# Sheet-QBOOST-v0_2.net
KiCad netlist of a schematic drawn in Altium Designer
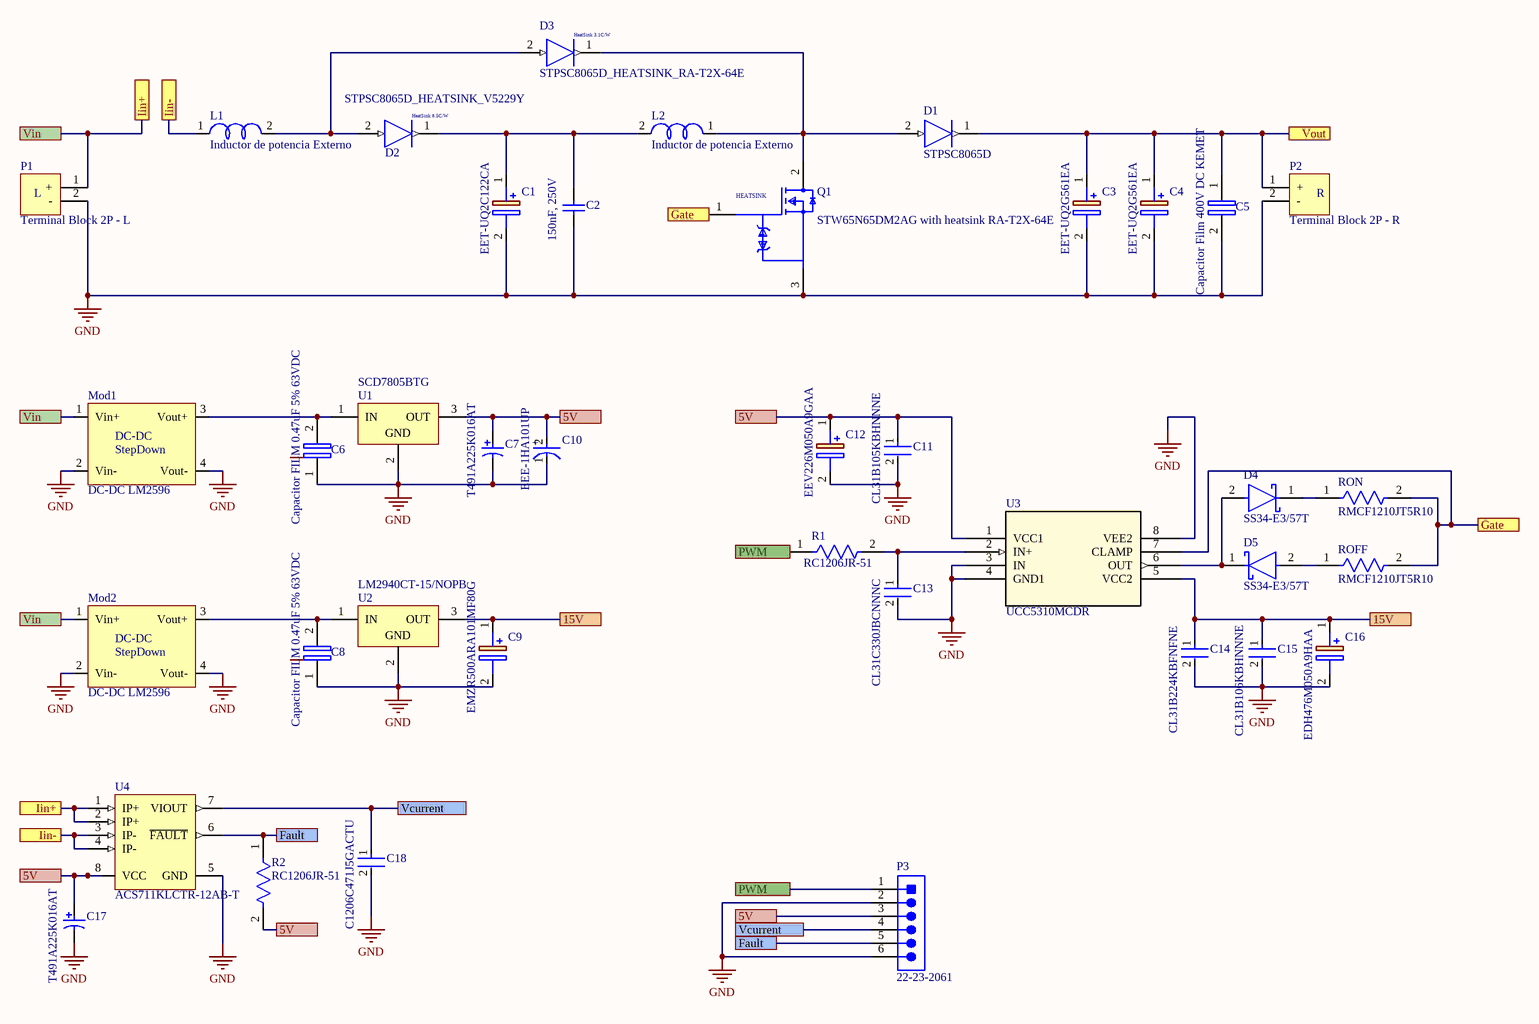
[diagram p0: Sheet-QBOOST-v0.2.SchDoc]

(export (version "E")
  (design (tool "Eeschema 10.0.6"))
  (components
    (comp (ref "C1")
      (value "EET-UQ2C122CA")
      (footprint "SamacSys:CAPPRD1000W200D2550H3700")
      (description "Capacitor Polarised")
      (libsource (lib "SamacSys") (part "EET-UQ2C122CA"))
    )
    (comp (ref "C2")
      (value "150nF, 250V")
      (footprint "WCAP-FTBP_L10.5W5H11")
      (description "WCAP-FTBP Film Capacitor, THT, L10.5W5H11, 150nF, 250V")
      (fields
        (field (name "MANUFACTURER") "Wurth Elektronik")
        (field (name "MANUFACTURER PART NUMBER") "890273322005CS")
      )
      (libsource (lib "890273322005CS_Alitum_WCAP-FTBP_rev20a") (part "890273322005CS"))
    )
    (comp (ref "C3")
      (value "EET-UQ2G561EA")
      (footprint "SamacSys:CAPPRD1000W200D3550H3700")
      (description "Capacitor Polarised")
      (libsource (lib "SamacSys") (part "EET-UQ2G561EA"))
    )
    (comp (ref "C4")
      (value "EET-UQ2G561EA")
      (footprint "SamacSys:CAPPRD1000W200D3550H3700")
      (description "Capacitor Polarised")
      (libsource (lib "SamacSys") (part "EET-UQ2G561EA"))
    )
    (comp (ref "C5")
      (value "Capacitor Film 400V DC KEMET")
      (footprint "Cap Film 18x5")
      (libsource (lib "CapFilm") (part "Cap film 400V DC 0.1uF"))
    )
    (comp (ref "C6")
      (value "Capacitor FILM 0.47uF 5% 63VDC")
      (footprint "Capacitor 5mm Radial")
      (libsource (lib "CAP FILM 0.47UF 5% 63VDC") (part "Capacitor FILM 0.47uF 5% 63VDC"))
    )
    (comp (ref "C7")
      (value "T491A225K016AT")
      (footprint "KEMT-T491-A_N")
      (description "Tantalum Capacitor, 2.2 uF, +/- 10%, 16 V, -55 to 125 degC, 2-Pin SMD, RoHS, Tape and Reel")
      (fields (field (name "VOLTAGE") "16VDC") (field (name "MANUFACTURER") "Kemet"))
      (libsource (lib "Altium Content Vault") (part "CAP-P-2"))
    )
    (comp (ref "C8")
      (value "Capacitor FILM 0.47uF 5% 63VDC")
      (footprint "Capacitor 5mm Radial")
      (libsource (lib "CAP FILM 0.47UF 5% 63VDC") (part "Capacitor FILM 0.47uF 5% 63VDC"))
    )
    (comp (ref "C9")
      (value "EMZR500ARA101MF80G")
      (footprint "CAP6.3X8")
      (description "CAP ALUM 100UF 20% 50V SMD")
      (libsource (lib "SamacSys") (part "EMZR500ARA101MF80G"))
    )
    (comp (ref "C10")
      (value "EEE-1HA101UP")
      (footprint "FP-SF-MFG")
      (description "CAP ALUM 100UF 20% 50V SMD")
      (fields
        (field (name "MANUFACTURER") "Panasonic")
        (field (name "OCTOPART") "https://octopart.com/eee-1ha101up-panasonic-55396734")
      )
      (libsource (lib "Altium Content Vault") (part "cf48714ba7e38822c1575c7ec0b6d1f"))
    )
    (comp (ref "C11")
      (value "CL31B105KBHNNNE")
      (footprint "FP-CL31-IPC_B")
      (description "Cap Ceramic 1uF 50V X7R ±10% SMD 1206 +125°C Embossed T/R")
      (fields (field (name "VOLTAGE") "50V") (field (name "TOLERANCE") "10%"))
      (libsource (lib "Altium Content Vault") (part "b4654b650e69147ec39a6b967a45e02"))
    )
    (comp (ref "C12")
      (value "EEV226M050A9GAA")
      (footprint "CAP6.3X5.65")
      (description "CAP ALUM SMD 105C 22UF 50VDC")
      (libsource (lib "SamacSys") (part "EEV226M050A9GAA"))
    )
    (comp (ref "C13")
      (value "CL31C330JBCNNNC")
      (footprint "FP-CL31-IPC_B")
      (description "Cap Ceramic 33pF 50V C0G ±5% SMD 1206 +125°C Embossed T/R")
      (fields (field (name "TOLERANCE") "5%") (field (name "VOLTAGE") "50V"))
      (libsource (lib "Altium Content Vault") (part "b4654b650e69147ec39a6b967a45e02"))
    )
    (comp (ref "C14")
      (value "CL31B224KBFNFNE")
      (footprint "FP-CL31-IPC_B")
      (description "Cap Ceramic 220nF 50V X7R ±10% SMD 1206 +125°C Embossed T/R")
      (fields (field (name "TOLERANCE") "10%"))
      (libsource (lib "Altium Content Vault") (part "b4654b650e69147ec39a6b967a45e02"))
    )
    (comp (ref "C15")
      (value "CL31B106KBHNNNE")
      (footprint "FP-CL31-IPC_B")
      (description "CAP CER 10UF 50V  X7R ±10% SMD 1206 +125°C Embossed T/R")
      (fields (field (name "TOLERANCE") "10%"))
      (libsource (lib "Altium Content Vault") (part "b4654b650e69147ec39a6b967a45e02"))
    )
    (comp (ref "C16")
      (value "EDH476M050A9HAA")
      (footprint "CAP6.3X8")
      (description "CAP ALUM SMD 105C 47UF 50VDC")
      (libsource (lib "SamacSys") (part "EDH476M050A9HAA"))
    )
    (comp (ref "C17")
      (value "T491A225K016AT")
      (footprint "KEMT-T491-A_N")
      (description "Tantalum Capacitor, 2.2 uF, +/- 10%, 16 V, -55 to 125 degC, 2-Pin SMD, RoHS, Tape and Reel")
      (fields (field (name "VOLTAGE") "16VDC") (field (name "MANUFACTURER") "Kemet"))
      (libsource (lib "Altium Content Vault") (part "CAP-P-2"))
    )
    (comp (ref "C18")
      (value "C1206C471J5GACTU")
      (footprint "FP-C1206C-EB-IPC_B")
      (description "1206 C 470pF Ceramic Multilayer Capacitor; 50 V; +125degC; C0G Dielectric; +/-5%")
      (fields
        (field (name "TOLERANCE") "0.05")
        (field (name "OCTOPART") "https://octopart.com/c1206c471j5gactu-kemet-123947")
      )
      (libsource (lib "Altium Content Vault") (part "b4654b650e69147ec39a6b967a45e02"))
    )
    (comp (ref "D1")
      (value "STPSC8065D")
      (footprint "SamacSys:TO505P460X1020X1968-2P")
      (description "Diode")
      (libsource (lib "SamacSys") (part "STPSC8065D"))
    )
    (comp (ref "D2")
      (value "STPSC8065D_HEATSINK_V5229Y")
      (footprint "TO505P460X1020X1968-2P - HEATSINK - V5229Y")
      (description "Diode with heatsink V5229Y")
      (fields (field (name "MANUFACTURER_PART_NUMBER") "STPSC8065D"))
      (libsource (lib "SamacSys") (part "STPSC8065D_HEATSINK_V5229Y"))
    )
    (comp (ref "D3")
      (value "STPSC8065D_HEATSINK_RA-T2X-64E")
      (footprint "TO505P460X1020X1968-2P - HEATSINK - RA-T2X-64E")
      (description "Diode with heatsink RA-T2X-64E")
      (fields (field (name "MANUFACTURER_PART_NUMBER") "STPSC8065D"))
      (libsource (lib "SamacSys") (part "STPSC8065D_HEATSINK_RA-T2X-64E"))
    )
    (comp (ref "D4")
      (value "SS34-E3/57T")
      (footprint "FP-95402-MFG")
      (description "DIODE SCHOTTKY 40V 3A DO214AB")
      (fields
        (field (name "MANUFACTURER") "Vishay")
        (field (name "OCTOPART") "https://octopart.com/ss34-e3%2F57t-vishay-39552907")
      )
      (libsource (lib "Altium Content Vault") (part "1d6ec82d83fb6aee721767c19dac4b9"))
    )
    (comp (ref "D5")
      (value "SS34-E3/57T")
      (footprint "FP-95402-MFG")
      (description "DIODE SCHOTTKY 40V 3A DO214AB")
      (fields
        (field (name "MANUFACTURER") "Vishay")
        (field (name "OCTOPART") "https://octopart.com/ss34-e3%2F57t-vishay-39552907")
      )
      (libsource (lib "Altium Content Vault") (part "1d6ec82d83fb6aee721767c19dac4b9"))
    )
    (comp (ref "L1")
      (value "Inductor de potencia Externo")
      (footprint "KF7.62-P3")
      (libsource (lib "") (part "Inductor_1"))
    )
    (comp (ref "L2")
      (value "Inductor de potencia Externo")
      (footprint "KF7.62-P3")
      (libsource (lib "Inductor externo") (part "Inductor"))
    )
    (comp (ref "Mod1")
      (value "DC-DC LM2596")
      (footprint "Mod 21x43 mm")
      (description "LM2596HV DC-DC Adjustable Step Down Buck Converter Power Module 4.5-50V To 3-35V Current limiting")
      (libsource (lib "ConverterDC-DC-LM2596") (part "DC-DC LM2596"))
    )
    (comp (ref "Mod2")
      (value "DC-DC LM2596")
      (footprint "Mod 21x43 mm")
      (description "LM2596HV DC-DC Adjustable Step Down Buck Converter Power Module 4.5-50V To 3-35V Current limiting")
      (libsource (lib "ConverterDC-DC-LM2596") (part "DC-DC LM2596"))
    )
    (comp (ref "P1")
      (value "Terminal Block 2P - L")
      (footprint "KF7.62-P2 - TB - L")
      (libsource (lib "Terminal Block") (part "Terminal Block 2P - L"))
    )
    (comp (ref "P2")
      (value "Terminal Block 2P - R")
      (footprint "KF7.62-P2 - TB - R")
      (libsource (lib "Terminal Block") (part "Terminal Block 2P - R"))
    )
    (comp (ref "P3")
      (value "22-23-2061")
      (footprint "MOLX-22-23-2061_V")
      (fields (field (name "MANUFACTURER") "Molex"))
      (libsource (lib "Altium Content Vault") (part "CN-1P-M-R6"))
    )
    (comp (ref "Q1")
      (value "STW65N65DM2AG with heatsink RA-T2X-64E")
      (footprint "FP-TO-247-0075325-MFG HEATSINK RA-T2X-64E")
      (description "MOSFET N-CH 650V 60A TO-247")
      (fields
        (field (name "MANUFACTURER") "STMicroelectronics")
        (field (name "MANUFACTURER PART NUMBER") "STW65N65DM2AG")
      )
      (libsource (lib "STW65N65DM2AG") (part "MOSFET N STW65N65DM2AG_HEATSINK"))
    )
    (comp (ref "R1")
      (value "RC1206JR-51")
      (footprint "FP-RC1206-IPC_B")
      (description "RES SMD 51 OHM  1/4W 1206")
      (fields
        (field (name "MANUFACTURER PART NUMBER") "RC1206JR-070RL")
        (field (name "MANUFACTURER") "YAGEO")
      )
      (libsource (lib "Altium Content Vault") (part "1029c3af85768c4190bb7ad29bc67b5"))
    )
    (comp (ref "R2")
      (value "RC1206JR-51")
      (footprint "FP-RC1206-IPC_B")
      (description "RES SMD 51 OHM  1/4W 1206")
      (fields
        (field (name "MANUFACTURER PART NUMBER") "RC1206JR-070RL")
        (field (name "MANUFACTURER") "YAGEO")
      )
      (libsource (lib "Altium Content Vault") (part "1029c3af85768c4190bb7ad29bc67b5"))
    )
    (comp (ref "ROFF")
      (value "RMCF1210JT5R10")
      (footprint "FP-RC3225-IPC_B")
      (description "RES 5.1 OHM 5% 1/2W 1210")
      (fields (field (name "TOLERANCE") "5%"))
      (libsource (lib "Altium Content Vault") (part "1029c3af85768c4190bb7ad29bc67b5"))
    )
    (comp (ref "RON")
      (value "RMCF1210JT5R10")
      (footprint "FP-RC3225-IPC_B")
      (description "RES 5.1 OHM 5% 1/2W 1210")
      (fields (field (name "TOLERANCE") "5%"))
      (libsource (lib "Altium Content Vault") (part "1029c3af85768c4190bb7ad29bc67b5"))
    )
    (comp (ref "U1")
      (value "SCD7805BTG")
      (footprint "T0220-3")
      (description "IC VOLT REG 1A 5V TO220 3-pin")
      (fields (field (name "MANUFACTURER") "On Semiconductor"))
      (libsource (lib "SCD7805") (part "SCD7805BTGOS-ND"))
    )
    (comp (ref "U2")
      (value "LM2940CT-15/NOPB")
      (footprint "T0220-3")
      (description "1A Low Dropout Regulator, 3-pin TO-220, Pb-Free")
      (fields (field (name "MANUFACTURER") "Texas Instruments"))
      (libsource (lib "LM2940-15") (part "CMP-0062-02546-3"))
    )
    (comp (ref "U3")
      (value "UCC5310MCDR")
      (footprint "D8_TEX")
      (description "No Description Available")
      (fields (field (name "COPYRIGHT") "Copyright (C) 2018 Accelerated Designs. All rights reserved"))
      (libsource (lib "UCC5310MCDR") (part "UCC5310MCDR"))
    )
    (comp (ref "U4")
      (value "ACS711KLCTR-12AB-T")
      (footprint "ALEG-LC-SOIC-8_V")
      (libsource (lib "ACS711KLCTR-12") (part "ACS711KLCTR-12AB-T"))
    )
  )
  (nets
    (net (code "1") (name "/5V") (class "Default")
      (node (ref "C10") (pin "2") (pinfunction "A_2") (pintype "passive"))
      (node (ref "C11") (pin "1") (pinfunction "1_1") (pintype "passive"))
      (node (ref "C12") (pin "1") (pinfunction "+_1") (pintype "passive"))
      (node (ref "C17") (pin "1") (pinfunction "1_1") (pintype "passive"))
      (node (ref "C7") (pin "1") (pinfunction "1_1") (pintype "passive"))
      (node (ref "P3") (pin "3") (pinfunction "3_3") (pintype "passive"))
      (node (ref "R2") (pin "2") (pinfunction "2_2") (pintype "passive"))
      (node (ref "U1") (pin "3") (pinfunction "OUT_3") (pintype "power_in"))
      (node (ref "U3") (pin "1") (pinfunction "VCC1_1") (pintype "power_in"))
      (node (ref "U4") (pin "8") (pinfunction "VCC_8") (pintype "power_in"))
    )
    (net (code "2") (name "/15V") (class "Default")
      (node (ref "C14") (pin "1") (pinfunction "1_1") (pintype "passive"))
      (node (ref "C15") (pin "1") (pinfunction "1_1") (pintype "passive"))
      (node (ref "C16") (pin "1") (pinfunction "+_1") (pintype "passive"))
      (node (ref "C9") (pin "1") (pinfunction "+_1") (pintype "passive"))
      (node (ref "U2") (pin "3") (pinfunction "OUT_3") (pintype "power_in"))
      (node (ref "U3") (pin "5") (pinfunction "VCC2_5") (pintype "power_in"))
    )
    (net (code "3") (name "/Fault") (class "Default")
      (node (ref "P3") (pin "5") (pinfunction "5_5") (pintype "passive"))
      (node (ref "R2") (pin "1") (pinfunction "1_1") (pintype "passive"))
      (node (ref "U4") (pin "6") (pinfunction "~{FAULT}_6") (pintype "output"))
    )
    (net (code "4") (name "/Gate") (class "Default")
      (node (ref "Q1") (pin "1") (pinfunction "G_1") (pintype "passive"))
      (node (ref "ROFF") (pin "2") (pinfunction "2_2") (pintype "passive"))
      (node (ref "RON") (pin "2") (pinfunction "2_2") (pintype "passive"))
      (node (ref "U3") (pin "7") (pinfunction "CLAMP_7") (pintype "passive"))
    )
    (net (code "5") (name "/Iin+") (class "Default")
      (node (ref "Mod1") (pin "1") (pinfunction "Vin+_1") (pintype "passive"))
      (node (ref "Mod2") (pin "1") (pinfunction "Vin+_1") (pintype "passive"))
      (node (ref "P1") (pin "1") (pinfunction "+_1") (pintype "passive"))
      (node (ref "U4") (pin "1") (pinfunction "IP+_1") (pintype "input"))
      (node (ref "U4") (pin "2") (pinfunction "IP+_2") (pintype "input"))
    )
    (net (code "6") (name "/Iin-") (class "Default")
      (node (ref "L1") (pin "1") (pintype "passive"))
      (node (ref "U4") (pin "3") (pinfunction "IP-_3") (pintype "input"))
      (node (ref "U4") (pin "4") (pinfunction "IP-_4") (pintype "input"))
    )
    (net (code "7") (name "/PWM") (class "Default")
      (node (ref "P3") (pin "1") (pinfunction "1_1") (pintype "passive"))
      (node (ref "R1") (pin "1") (pinfunction "1_1") (pintype "passive"))
    )
    (net (code "8") (name "/Vcurrent") (class "Default")
      (node (ref "C18") (pin "1") (pinfunction "1_1") (pintype "passive"))
      (node (ref "P3") (pin "4") (pinfunction "4_4") (pintype "passive"))
      (node (ref "U4") (pin "7") (pinfunction "VIOUT_7") (pintype "output"))
    )
    (net (code "9") (name "/Vout") (class "Default")
      (node (ref "C3") (pin "1") (pinfunction "+_1") (pintype "power_in"))
      (node (ref "C4") (pin "1") (pinfunction "+_1") (pintype "power_in"))
      (node (ref "C5") (pin "1") (pintype "passive"))
      (node (ref "D1") (pin "1") (pinfunction "K_1") (pintype "output"))
      (node (ref "P2") (pin "1") (pinfunction "+_1") (pintype "passive"))
    )
    (net (code "10") (name "GND") (class "Default")
      (node (ref "C1") (pin "2") (pinfunction "-_2") (pintype "power_in"))
      (node (ref "C10") (pin "1") (pinfunction "C_1") (pintype "passive"))
      (node (ref "C11") (pin "2") (pinfunction "2_2") (pintype "passive"))
      (node (ref "C12") (pin "2") (pinfunction "-_2") (pintype "passive"))
      (node (ref "C13") (pin "2") (pinfunction "2_2") (pintype "passive"))
      (node (ref "C14") (pin "2") (pinfunction "2_2") (pintype "passive"))
      (node (ref "C15") (pin "2") (pinfunction "2_2") (pintype "passive"))
      (node (ref "C16") (pin "2") (pinfunction "-_2") (pintype "passive"))
      (node (ref "C17") (pin "2") (pinfunction "2_2") (pintype "passive"))
      (node (ref "C18") (pin "2") (pinfunction "2_2") (pintype "passive"))
      (node (ref "C2") (pin "1") (pinfunction "1_1") (pintype "passive"))
      (node (ref "C3") (pin "2") (pinfunction "-_2") (pintype "power_in"))
      (node (ref "C4") (pin "2") (pinfunction "-_2") (pintype "power_in"))
      (node (ref "C5") (pin "2") (pintype "passive"))
      (node (ref "C6") (pin "1") (pintype "passive"))
      (node (ref "C7") (pin "2") (pinfunction "2_2") (pintype "passive"))
      (node (ref "C8") (pin "1") (pintype "passive"))
      (node (ref "C9") (pin "2") (pinfunction "-_2") (pintype "passive"))
      (node (ref "Mod1") (pin "2") (pinfunction "Vin-_2") (pintype "passive"))
      (node (ref "Mod1") (pin "4") (pinfunction "Vout-_4") (pintype "passive"))
      (node (ref "Mod2") (pin "2") (pinfunction "Vin-_2") (pintype "passive"))
      (node (ref "Mod2") (pin "4") (pinfunction "Vout-_4") (pintype "passive"))
      (node (ref "P1") (pin "2") (pinfunction "-_2") (pintype "passive"))
      (node (ref "P2") (pin "2") (pinfunction "-_2") (pintype "passive"))
      (node (ref "P3") (pin "2") (pinfunction "2_2") (pintype "passive"))
      (node (ref "P3") (pin "6") (pinfunction "6_6") (pintype "passive"))
      (node (ref "Q1") (pin "3") (pinfunction "S_3") (pintype "passive"))
      (node (ref "U1") (pin "2") (pinfunction "GND_2") (pintype "power_in"))
      (node (ref "U2") (pin "2") (pinfunction "GND_2") (pintype "power_in"))
      (node (ref "U3") (pin "3") (pinfunction "IN_3") (pintype "passive"))
      (node (ref "U3") (pin "4") (pinfunction "GND1_4") (pintype "passive"))
      (node (ref "U3") (pin "8") (pinfunction "VEE2_8") (pintype "power_in"))
      (node (ref "U4") (pin "5") (pinfunction "GND_5") (pintype "power_in"))
    )
    (net (code "11") (name "Net-(C1-+)") (class "Default")
      (node (ref "C1") (pin "1") (pinfunction "+_1") (pintype "power_in"))
      (node (ref "C2") (pin "2") (pinfunction "2_2") (pintype "passive"))
      (node (ref "D2") (pin "1") (pinfunction "K_1") (pintype "output"))
      (node (ref "L2") (pin "2") (pintype "passive"))
    )
    (net (code "12") (name "Net-(D1-A)") (class "Default")
      (node (ref "D1") (pin "2") (pinfunction "A_2") (pintype "input"))
      (node (ref "D3") (pin "1") (pinfunction "K_1") (pintype "output"))
      (node (ref "L2") (pin "1") (pintype "passive"))
      (node (ref "Q1") (pin "2") (pinfunction "D_2") (pintype "passive"))
    )
    (net (code "13") (name "Net-(D2-A)") (class "Default")
      (node (ref "D2") (pin "2") (pinfunction "A_2") (pintype "input"))
      (node (ref "D3") (pin "2") (pinfunction "A_2") (pintype "input"))
      (node (ref "L1") (pin "2") (pintype "passive"))
    )
    (net (code "14") (name "Net-(D4-A)") (class "Default")
      (node (ref "D4") (pin "2") (pinfunction "A_2") (pintype "passive"))
      (node (ref "D5") (pin "1") (pinfunction "C_1") (pintype "passive"))
      (node (ref "U3") (pin "6") (pinfunction "OUT_6") (pintype "output"))
    )
    (net (code "15") (name "Net-(D4-C)") (class "Default")
      (node (ref "D4") (pin "1") (pinfunction "C_1") (pintype "passive"))
      (node (ref "RON") (pin "1") (pinfunction "1_1") (pintype "passive"))
    )
    (net (code "16") (name "Net-(D5-A)") (class "Default")
      (node (ref "D5") (pin "2") (pinfunction "A_2") (pintype "passive"))
      (node (ref "ROFF") (pin "1") (pinfunction "1_1") (pintype "passive"))
    )
    (net (code "17") (name "Net-(Mod1-Vout+)") (class "Default")
      (node (ref "C6") (pin "2") (pintype "passive"))
      (node (ref "Mod1") (pin "3") (pinfunction "Vout+_3") (pintype "passive"))
      (node (ref "U1") (pin "1") (pinfunction "IN_1") (pintype "power_in"))
    )
    (net (code "18") (name "Net-(Mod2-Vout+)") (class "Default")
      (node (ref "C8") (pin "2") (pintype "passive"))
      (node (ref "Mod2") (pin "3") (pinfunction "Vout+_3") (pintype "passive"))
      (node (ref "U2") (pin "1") (pinfunction "IN_1") (pintype "power_in"))
    )
    (net (code "19") (name "Net-(U3-IN+)") (class "Default")
      (node (ref "C13") (pin "1") (pinfunction "1_1") (pintype "passive"))
      (node (ref "R1") (pin "2") (pinfunction "2_2") (pintype "passive"))
      (node (ref "U3") (pin "2") (pinfunction "IN+_2") (pintype "input"))
    )
  )
)
